# sensor.net
KiCad netlist of a schematic drawn in EAGLE
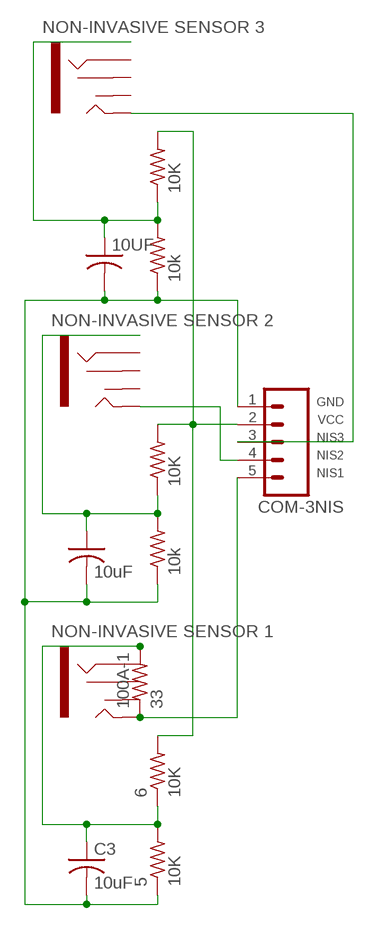
[diagram p0: schematic, sheet 1]

(export (version "E")
  (design (tool "Eeschema 10.0.6"))
  (components
    (comp (ref "1")
      (value "10k")
      (footprint "eagle-import:M0805")
      (libsource (lib "eagle-import") (part "R-US_M0805"))
    )
    (comp (ref "2")
      (value "10K")
      (footprint "eagle-import:M0805")
      (libsource (lib "eagle-import") (part "R-US_M0805"))
    )
    (comp (ref "3")
      (value "10k")
      (footprint "eagle-import:M0805")
      (libsource (lib "eagle-import") (part "R-US_M0805"))
    )
    (comp (ref "4")
      (value "10K")
      (footprint "eagle-import:M0805")
      (libsource (lib "eagle-import") (part "R-US_M0805"))
    )
    (comp (ref "5")
      (value "10K")
      (footprint "eagle-import:M0805")
      (libsource (lib "eagle-import") (part "R-US_M0805"))
    )
    (comp (ref "6")
      (value "10K")
      (footprint "eagle-import:M0805")
      (libsource (lib "eagle-import") (part "R-US_M0805"))
    )
    (comp (ref "10UF")
      (value "C-USC0805K")
      (footprint "eagle-import:C0805K")
      (libsource (lib "eagle-import") (part "C-USC0805K"))
    )
    (comp (ref "100A-1")
      (value "33")
      (footprint "eagle-import:M0805")
      (libsource (lib "eagle-import") (part "R-US_M0805"))
    )
    (comp (ref "C2")
      (value "10uF")
      (footprint "eagle-import:C0805K")
      (libsource (lib "eagle-import") (part "C-USC0805K"))
    )
    (comp (ref "C3")
      (value "10uF")
      (footprint "eagle-import:C0805K")
      (libsource (lib "eagle-import") (part "C-USC0805K"))
    )
    (comp (ref "COM-3NIS")
      (value "M05PTH")
      (footprint "eagle-import:1X05")
      (libsource (lib "eagle-import") (part "M05PTH"))
    )
    (comp (ref "U1")
      (value "NON-INVASIVE SENSOR 1")
      (footprint "eagle-import:AUDIO-JACK")
      (libsource (lib "eagle-import") (part "AUDIO-JACK2PTH"))
    )
    (comp (ref "U2")
      (value "NON-INVASIVE SENSOR 2")
      (footprint "eagle-import:AUDIO-JACK")
      (libsource (lib "eagle-import") (part "AUDIO-JACK2PTH"))
    )
    (comp (ref "U3")
      (value "NON-INVASIVE SENSOR 3")
      (footprint "eagle-import:AUDIO-JACK")
      (libsource (lib "eagle-import") (part "AUDIO-JACK2PTH"))
    )
  )
  (nets
    (net (code "1") (name "/GND") (class "Default")
      (node (ref "2") (pin "2") (pinfunction "2_2") (pintype "passive"))
      (node (ref "4") (pin "2") (pinfunction "2_2") (pintype "passive"))
      (node (ref "6") (pin "2") (pinfunction "2_2") (pintype "passive"))
      (node (ref "COM-3NIS") (pin "2") (pinfunction "2_2") (pintype "passive"))
    )
    (net (code "2") (name "/NIS1") (class "Default")
      (node (ref "100A-1") (pin "1") (pinfunction "1_1") (pintype "passive"))
      (node (ref "COM-3NIS") (pin "5") (pinfunction "5_5") (pintype "passive"))
      (node (ref "U1") (pin "TIP") (pinfunction "TIP_TIP") (pintype "bidirectional"))
    )
    (net (code "3") (name "/NIS2") (class "Default")
      (node (ref "COM-3NIS") (pin "4") (pinfunction "4_4") (pintype "passive"))
      (node (ref "U2") (pin "TIP") (pinfunction "TIP_TIP") (pintype "bidirectional"))
    )
    (net (code "4") (name "/NIS3") (class "Default")
      (node (ref "COM-3NIS") (pin "3") (pinfunction "3_3") (pintype "passive"))
      (node (ref "U3") (pin "TIP") (pinfunction "TIP_TIP") (pintype "bidirectional"))
    )
    (net (code "5") (name "/VCC") (class "Default")
      (node (ref "1") (pin "1") (pinfunction "1_1") (pintype "passive"))
      (node (ref "10UF") (pin "2") (pinfunction "2_2") (pintype "passive"))
      (node (ref "3") (pin "1") (pinfunction "1_1") (pintype "passive"))
      (node (ref "5") (pin "1") (pinfunction "1_1") (pintype "passive"))
      (node (ref "C2") (pin "2") (pinfunction "2_2") (pintype "passive"))
      (node (ref "C3") (pin "2") (pinfunction "2_2") (pintype "passive"))
      (node (ref "COM-3NIS") (pin "1") (pinfunction "1_1") (pintype "passive"))
    )
    (net (code "6") (name "Net-(1-Pad2)") (class "Default")
      (node (ref "1") (pin "2") (pinfunction "2_2") (pintype "passive"))
      (node (ref "10UF") (pin "1") (pinfunction "1_1") (pintype "passive"))
      (node (ref "2") (pin "1") (pinfunction "1_1") (pintype "passive"))
      (node (ref "U3") (pin "SLEEVE") (pinfunction "SLEEVE_SLEEVE") (pintype "bidirectional"))
    )
    (net (code "7") (name "Net-(3-Pad2)") (class "Default")
      (node (ref "3") (pin "2") (pinfunction "2_2") (pintype "passive"))
      (node (ref "4") (pin "1") (pinfunction "1_1") (pintype "passive"))
      (node (ref "C2") (pin "1") (pinfunction "1_1") (pintype "passive"))
      (node (ref "U2") (pin "SLEEVE") (pinfunction "SLEEVE_SLEEVE") (pintype "bidirectional"))
    )
    (net (code "8") (name "Net-(100A-1-Pad2)") (class "Default")
      (node (ref "100A-1") (pin "2") (pinfunction "2_2") (pintype "passive"))
      (node (ref "5") (pin "2") (pinfunction "2_2") (pintype "passive"))
      (node (ref "6") (pin "1") (pinfunction "1_1") (pintype "passive"))
      (node (ref "C3") (pin "1") (pinfunction "1_1") (pintype "passive"))
      (node (ref "U1") (pin "SLEEVE") (pinfunction "SLEEVE_SLEEVE") (pintype "bidirectional"))
    )
    (net (code "9") (name "unconnected-(U1-PadRING)") (class "Default")
      (node (ref "U1") (pin "RING") (pinfunction "RING_RING") (pintype "bidirectional"))
    )
    (net (code "10") (name "unconnected-(U1-PadRSH)") (class "Default")
      (node (ref "U1") (pin "RSH") (pinfunction "RSH_RSH") (pintype "bidirectional"))
    )
    (net (code "11") (name "unconnected-(U1-PadTSH)") (class "Default")
      (node (ref "U1") (pin "TSH") (pinfunction "TSH_TSH") (pintype "bidirectional"))
    )
    (net (code "12") (name "unconnected-(U2-PadRING)") (class "Default")
      (node (ref "U2") (pin "RING") (pinfunction "RING_RING") (pintype "bidirectional"))
    )
    (net (code "13") (name "unconnected-(U2-PadRSH)") (class "Default")
      (node (ref "U2") (pin "RSH") (pinfunction "RSH_RSH") (pintype "bidirectional"))
    )
    (net (code "14") (name "unconnected-(U2-PadTSH)") (class "Default")
      (node (ref "U2") (pin "TSH") (pinfunction "TSH_TSH") (pintype "bidirectional"))
    )
    (net (code "15") (name "unconnected-(U3-PadRING)") (class "Default")
      (node (ref "U3") (pin "RING") (pinfunction "RING_RING") (pintype "bidirectional"))
    )
    (net (code "16") (name "unconnected-(U3-PadRSH)") (class "Default")
      (node (ref "U3") (pin "RSH") (pinfunction "RSH_RSH") (pintype "bidirectional"))
    )
    (net (code "17") (name "unconnected-(U3-PadTSH)") (class "Default")
      (node (ref "U3") (pin "TSH") (pinfunction "TSH_TSH") (pintype "bidirectional"))
    )
  )
)
